# Sheet1_GMAX4651_MB.net
KiCad netlist of a schematic drawn in Altium Designer
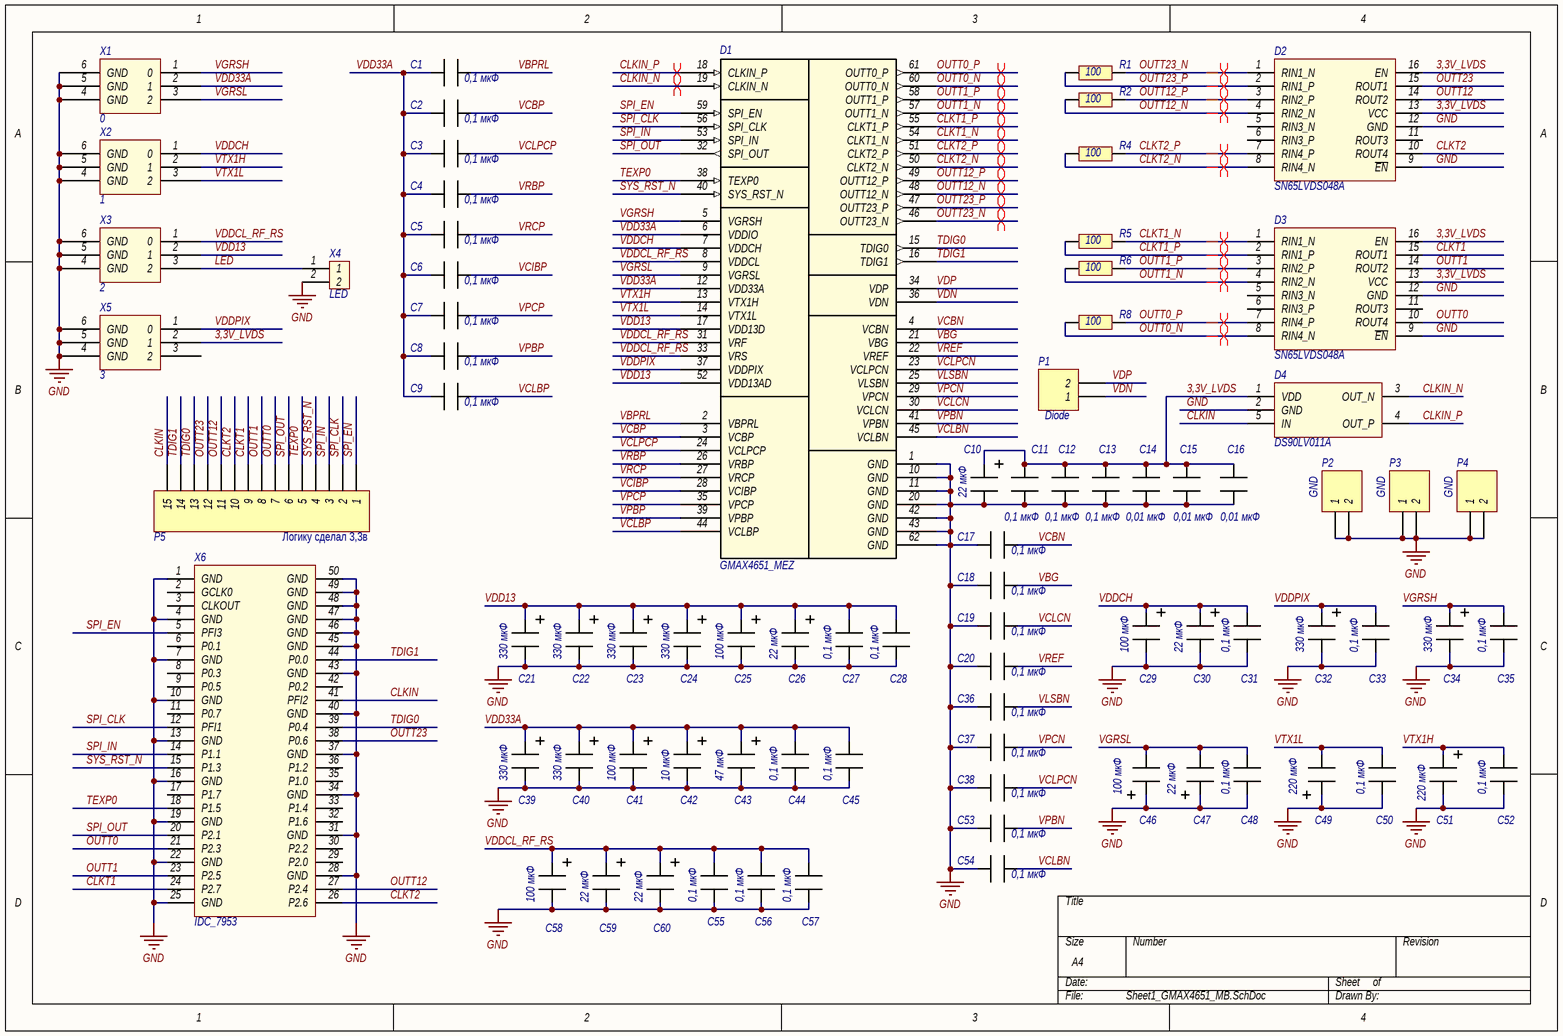
[diagram p0: Sheet1_GMAX4651_MB.SchDoc]

(export (version "E")
  (design (tool "Eeschema 10.0.6"))
  (components
    (comp (ref "C1") (value "0,1 мкФ") (footprint "CAP_SMALL") (libsource (lib "Schlib") (part "CAP_SMALL")))
    (comp (ref "C2") (value "0,1 мкФ") (footprint "CAP_SMALL") (libsource (lib "Schlib") (part "CAP_SMALL")))
    (comp (ref "C3") (value "0,1 мкФ") (footprint "CAP_SMALL") (libsource (lib "Schlib") (part "CAP_SMALL")))
    (comp (ref "C4") (value "0,1 мкФ") (footprint "CAP_SMALL") (libsource (lib "Schlib") (part "CAP_SMALL")))
    (comp (ref "C5") (value "0,1 мкФ") (footprint "CAP_SMALL") (libsource (lib "Schlib") (part "CAP_SMALL")))
    (comp (ref "C6") (value "0,1 мкФ") (footprint "CAP_SMALL") (libsource (lib "Schlib") (part "CAP_SMALL")))
    (comp (ref "C7") (value "0,1 мкФ") (footprint "CAP_SMALL") (libsource (lib "Schlib") (part "CAP_SMALL")))
    (comp (ref "C8") (value "0,1 мкФ") (footprint "CAP_SMALL") (libsource (lib "Schlib") (part "CAP_SMALL")))
    (comp (ref "C9") (value "0,1 мкФ") (footprint "CAP_SMALL") (libsource (lib "Schlib") (part "CAP_SMALL")))
    (comp (ref "C10")
      (value "22 мкФ")
      (footprint "Cap_0511_electrolitic")
      (libsource (lib "Schlib") (part "Cap_electrolotoc_0511"))
    )
    (comp (ref "C11") (value "0,1 мкФ") (footprint "CAP_SMALL") (libsource (lib "Schlib") (part "CAP_SMALL")))
    (comp (ref "C12") (value "0,1 мкФ") (footprint "CAP_SMALL") (libsource (lib "Schlib") (part "CAP_SMALL")))
    (comp (ref "C13") (value "0,1 мкФ") (footprint "CAP_SMALL") (libsource (lib "Schlib") (part "CAP_SMALL")))
    (comp (ref "C14")
      (value "0,01 мкФ")
      (footprint "CAP_SMALL")
      (libsource (lib "Schlib") (part "CAP_SMALL"))
    )
    (comp (ref "C15")
      (value "0,01 мкФ")
      (footprint "CAP_SMALL")
      (libsource (lib "Schlib") (part "CAP_SMALL"))
    )
    (comp (ref "C16")
      (value "0,01 мкФ")
      (footprint "CAP_SMALL")
      (libsource (lib "Schlib") (part "CAP_SMALL"))
    )
    (comp (ref "C17") (value "0,1 мкФ") (footprint "CAP_SMALL") (libsource (lib "Schlib") (part "CAP_SMALL")))
    (comp (ref "C18") (value "0,1 мкФ") (footprint "CAP_SMALL") (libsource (lib "Schlib") (part "CAP_SMALL")))
    (comp (ref "C19") (value "0,1 мкФ") (footprint "CAP_SMALL") (libsource (lib "Schlib") (part "CAP_SMALL")))
    (comp (ref "C20") (value "0,1 мкФ") (footprint "CAP_SMALL") (libsource (lib "Schlib") (part "CAP_SMALL")))
    (comp (ref "C21")
      (value "330 мкФ")
      (footprint "Cap_1013_electrolitic")
      (libsource (lib "Schlib") (part "Cap_electrolotoc_1013"))
    )
    (comp (ref "C22")
      (value "330 мкФ")
      (footprint "Cap_1013_electrolitic")
      (libsource (lib "Schlib") (part "Cap_electrolotoc_1013"))
    )
    (comp (ref "C23")
      (value "330 мкФ")
      (footprint "Cap_1013_electrolitic")
      (libsource (lib "Schlib") (part "Cap_electrolotoc_1013"))
    )
    (comp (ref "C24")
      (value "330 мкФ")
      (footprint "Cap_1013_electrolitic")
      (libsource (lib "Schlib") (part "Cap_electrolotoc_1013"))
    )
    (comp (ref "C25")
      (value "100 мкФ")
      (footprint "Cap_0612_electrolitic")
      (libsource (lib "Schlib") (part "Cap_electrolotoc_0612"))
    )
    (comp (ref "C26")
      (value "22 мкФ")
      (footprint "Cap_0511_electrolitic")
      (libsource (lib "Schlib") (part "Cap_electrolotoc_0511"))
    )
    (comp (ref "C27") (value "0,1 мкФ") (footprint "CAP_SMALL") (libsource (lib "Schlib") (part "CAP_SMALL")))
    (comp (ref "C28") (value "0,1 мкФ") (footprint "CAP_SMALL") (libsource (lib "Schlib") (part "CAP_SMALL")))
    (comp (ref "C29")
      (value "100 мкФ")
      (footprint "Cap_0612_electrolitic")
      (libsource (lib "Schlib") (part "Cap_electrolotoc_0612"))
    )
    (comp (ref "C30")
      (value "22 мкФ")
      (footprint "Cap_0511_electrolitic")
      (libsource (lib "Schlib") (part "Cap_electrolotoc_0511"))
    )
    (comp (ref "C31") (value "0,1 мкФ") (footprint "CAP_SMALL") (libsource (lib "Schlib") (part "CAP_SMALL")))
    (comp (ref "C32")
      (value "330 мкФ")
      (footprint "Cap_1013_electrolitic")
      (libsource (lib "Schlib") (part "Cap_electrolotoc_1013"))
    )
    (comp (ref "C33") (value "0,1 мкФ") (footprint "CAP_SMALL") (libsource (lib "Schlib") (part "CAP_SMALL")))
    (comp (ref "C34")
      (value "330 мкФ")
      (footprint "Cap_1013_electrolitic")
      (libsource (lib "Schlib") (part "Cap_electrolotoc_1013"))
    )
    (comp (ref "C35") (value "0,1 мкФ") (footprint "CAP_SMALL") (libsource (lib "Schlib") (part "CAP_SMALL")))
    (comp (ref "C36") (value "0,1 мкФ") (footprint "CAP_SMALL") (libsource (lib "Schlib") (part "CAP_SMALL")))
    (comp (ref "C37") (value "0,1 мкФ") (footprint "CAP_SMALL") (libsource (lib "Schlib") (part "CAP_SMALL")))
    (comp (ref "C38") (value "0,1 мкФ") (footprint "CAP_SMALL") (libsource (lib "Schlib") (part "CAP_SMALL")))
    (comp (ref "C39")
      (value "330 мкФ")
      (footprint "Cap_1013_electrolitic")
      (libsource (lib "Schlib") (part "Cap_electrolotoc_1013"))
    )
    (comp (ref "C40")
      (value "330 мкФ")
      (footprint "Cap_1013_electrolitic")
      (libsource (lib "Schlib") (part "Cap_electrolotoc_1013"))
    )
    (comp (ref "C41")
      (value "100 мкФ")
      (footprint "Cap_0612_electrolitic")
      (libsource (lib "Schlib") (part "Cap_electrolotoc_0612"))
    )
    (comp (ref "C42")
      (value "10 мкФ")
      (footprint "Cap_0511_electrolitic")
      (libsource (lib "Schlib") (part "Cap_electrolotoc_0511"))
    )
    (comp (ref "C43")
      (value "47 мкФ")
      (footprint "Cap_0612_electrolitic")
      (libsource (lib "Schlib") (part "Cap_electrolotoc_0612"))
    )
    (comp (ref "C44") (value "0,1 мкФ") (footprint "CAP_SMALL") (libsource (lib "Schlib") (part "CAP_SMALL")))
    (comp (ref "C45") (value "0,1 мкФ") (footprint "CAP_SMALL") (libsource (lib "Schlib") (part "CAP_SMALL")))
    (comp (ref "C46")
      (value "100 мкФ")
      (footprint "Cap_0612_electrolitic")
      (libsource (lib "Schlib") (part "Cap_electrolotoc_0612"))
    )
    (comp (ref "C47")
      (value "22 мкФ")
      (footprint "Cap_0511_electrolitic")
      (libsource (lib "Schlib") (part "Cap_electrolotoc_0511"))
    )
    (comp (ref "C48") (value "0,1 мкФ") (footprint "CAP_SMALL") (libsource (lib "Schlib") (part "CAP_SMALL")))
    (comp (ref "C49")
      (value "220 мкФ")
      (footprint "Cap_1013_electrolitic")
      (libsource (lib "Schlib") (part "Cap_electrolotoc_1013"))
    )
    (comp (ref "C50") (value "0,1 мкФ") (footprint "CAP_SMALL") (libsource (lib "Schlib") (part "CAP_SMALL")))
    (comp (ref "C51")
      (value "220 мкФ")
      (footprint "Cap_1013_electrolitic")
      (libsource (lib "Schlib") (part "Cap_electrolotoc_1013"))
    )
    (comp (ref "C52") (value "0,1 мкФ") (footprint "CAP_SMALL") (libsource (lib "Schlib") (part "CAP_SMALL")))
    (comp (ref "C53") (value "0,1 мкФ") (footprint "CAP_SMALL") (libsource (lib "Schlib") (part "CAP_SMALL")))
    (comp (ref "C54") (value "0,1 мкФ") (footprint "CAP_SMALL") (libsource (lib "Schlib") (part "CAP_SMALL")))
    (comp (ref "C55") (value "0,1 мкФ") (footprint "CAP_SMALL") (libsource (lib "Schlib") (part "CAP_SMALL")))
    (comp (ref "C56") (value "0,1 мкФ") (footprint "CAP_SMALL") (libsource (lib "Schlib") (part "CAP_SMALL")))
    (comp (ref "C57") (value "0,1 мкФ") (footprint "CAP_SMALL") (libsource (lib "Schlib") (part "CAP_SMALL")))
    (comp (ref "C58")
      (value "100 мкФ")
      (footprint "Cap_0612_electrolitic")
      (libsource (lib "Schlib") (part "Cap_electrolotoc_0612"))
    )
    (comp (ref "C59")
      (value "22 мкФ")
      (footprint "Cap_0511_electrolitic")
      (libsource (lib "Schlib") (part "Cap_electrolotoc_0511"))
    )
    (comp (ref "C60")
      (value "22 мкФ")
      (footprint "Cap_0511_electrolitic")
      (libsource (lib "Schlib") (part "Cap_electrolotoc_0511"))
    )
    (comp (ref "D1")
      (value "GMAX4651_MEZ")
      (footprint "GMAX4651_MEZ")
      (libsource (lib "Schlib") (part "GMAX4651_MEZ"))
    )
    (comp (ref "D2")
      (value "SN65LVDS048A")
      (footprint "SN65LVDS048A (4LVDS)")
      (libsource (lib "Schlib") (part "SN65LVDS048A (4LVDS)"))
    )
    (comp (ref "D3")
      (value "SN65LVDS048A")
      (footprint "SN65LVDS048A (4LVDS)")
      (libsource (lib "Schlib") (part "SN65LVDS048A (4LVDS)"))
    )
    (comp (ref "D4")
      (value "DS90LV011A")
      (footprint "DS90LV011A")
      (description "LVDS Driver 1 ch")
      (libsource (lib "Schlib") (part "DS90LV011A"))
    )
    (comp (ref "P1")
      (value "Diode")
      (footprint "HDR1X2")
      (description "Header, 2-Pin")
      (fields (field (name "PUBLISHER") "Altium Limited"))
      (libsource (lib "Miscellaneous Connectors") (part "Header 2"))
    )
    (comp (ref "P2")
      (value "GND")
      (footprint "HDR1X2")
      (description "Header, 2-Pin")
      (fields (field (name "PUBLISHER") "Altium Limited"))
      (libsource (lib "") (part "Header 2_1"))
    )
    (comp (ref "P3")
      (value "GND")
      (footprint "HDR1X2")
      (description "Header, 2-Pin")
      (fields (field (name "PUBLISHER") "Altium Limited"))
      (libsource (lib "") (part "Header 2_1"))
    )
    (comp (ref "P4")
      (value "GND")
      (footprint "HDR1X2")
      (description "Header, 2-Pin")
      (fields (field (name "PUBLISHER") "Altium Limited"))
      (libsource (lib "") (part "Header 2_1"))
    )
    (comp (ref "P5")
      (value "Header 15")
      (footprint "HDR1X15")
      (description "Header, 15-Pin")
      (fields (field (name "PUBLISHER") "Altium Limited"))
      (libsource (lib "Miscellaneous Connectors") (part "Header 15"))
    )
    (comp (ref "R1") (value "100") (footprint "RES") (libsource (lib "Schlib") (part "RES")))
    (comp (ref "R2") (value "100") (footprint "RES") (libsource (lib "Schlib") (part "RES")))
    (comp (ref "R4") (value "100") (footprint "RES") (libsource (lib "Schlib") (part "RES")))
    (comp (ref "R5") (value "100") (footprint "RES") (libsource (lib "Schlib") (part "RES")))
    (comp (ref "R6") (value "100") (footprint "RES") (libsource (lib "Schlib") (part "RES")))
    (comp (ref "R8") (value "100") (footprint "RES") (libsource (lib "Schlib") (part "RES")))
    (comp (ref "X1") (value "0") (footprint "POWER") (libsource (lib "Schlib") (part "POWER")))
    (comp (ref "X2") (value "1") (footprint "POWER") (libsource (lib "Schlib") (part "POWER")))
    (comp (ref "X3") (value "2") (footprint "POWER") (libsource (lib "Schlib") (part "POWER")))
    (comp (ref "X4") (value "LED") (footprint "KLEMMNIK_2") (libsource (lib "Schlib") (part "KLEMMNIK_2")))
    (comp (ref "X5") (value "3") (footprint "POWER") (libsource (lib "Schlib") (part "POWER")))
    (comp (ref "X6") (value "IDC_7953") (footprint "IDC_7953") (libsource (lib "VPL") (part "IDC_7953")))
  )
  (nets
    (net (code "1") (name "/3,3V_LVDS") (class "Default")
      (node (ref "C10") (pin "1") (pinfunction "1_1") (pintype "passive"))
      (node (ref "C11") (pin "2") (pinfunction "2_2") (pintype "passive"))
      (node (ref "C12") (pin "2") (pinfunction "2_2") (pintype "passive"))
      (node (ref "C13") (pin "2") (pinfunction "2_2") (pintype "passive"))
      (node (ref "C14") (pin "2") (pinfunction "2_2") (pintype "passive"))
      (node (ref "C15") (pin "2") (pinfunction "2_2") (pintype "passive"))
      (node (ref "C16") (pin "2") (pinfunction "2_2") (pintype "passive"))
      (node (ref "D2") (pin "13") (pinfunction "VCC_13") (pintype "passive"))
      (node (ref "D2") (pin "16") (pinfunction "EN_16") (pintype "passive"))
      (node (ref "D3") (pin "13") (pinfunction "VCC_13") (pintype "passive"))
      (node (ref "D3") (pin "16") (pinfunction "EN_16") (pintype "passive"))
      (node (ref "D4") (pin "1") (pinfunction "VDD_1") (pintype "passive"))
      (node (ref "X5") (pin "2") (pinfunction "1_2") (pintype "passive"))
    )
    (net (code "2") (name "/CLKIN") (class "Default")
      (node (ref "D4") (pin "5") (pinfunction "IN_5") (pintype "passive"))
      (node (ref "P5") (pin "15") (pinfunction "15_15") (pintype "passive"))
      (node (ref "X6") (pin "41") (pinfunction "PFI2_41") (pintype "passive"))
    )
    (net (code "3") (name "/CLKIN_N") (class "Default")
      (node (ref "D1") (pin "19") (pinfunction "CLKIN_N_19") (pintype "input"))
      (node (ref "D4") (pin "3") (pinfunction "OUT_N_3") (pintype "passive"))
    )
    (net (code "4") (name "/CLKIN_P") (class "Default")
      (node (ref "D1") (pin "18") (pinfunction "CLKIN_P_18") (pintype "input"))
      (node (ref "D4") (pin "4") (pinfunction "OUT_P_4") (pintype "passive"))
    )
    (net (code "5") (name "/CLKT1") (class "Default")
      (node (ref "D3") (pin "15") (pinfunction "ROUT1_15") (pintype "passive"))
      (node (ref "P5") (pin "9") (pinfunction "9_9") (pintype "passive"))
      (node (ref "X6") (pin "24") (pinfunction "P2.7_24") (pintype "passive"))
    )
    (net (code "6") (name "/CLKT1_N") (class "Default")
      (node (ref "D1") (pin "54") (pinfunction "CLKT1_N_54") (pintype "output"))
      (node (ref "D3") (pin "1") (pinfunction "RIN1_N_1") (pintype "passive"))
      (node (ref "R5") (pin "1") (pinfunction "1_1") (pintype "passive"))
    )
    (net (code "7") (name "/CLKT1_P") (class "Default")
      (node (ref "D1") (pin "55") (pinfunction "CLKT1_P_55") (pintype "output"))
      (node (ref "D3") (pin "2") (pinfunction "RIN1_P_2") (pintype "passive"))
      (node (ref "R5") (pin "2") (pinfunction "2_2") (pintype "passive"))
    )
    (net (code "8") (name "/CLKT2") (class "Default")
      (node (ref "D2") (pin "10") (pinfunction "ROUT4_10") (pintype "passive"))
      (node (ref "P5") (pin "10") (pinfunction "10_10") (pintype "passive"))
      (node (ref "X6") (pin "26") (pinfunction "P2.6_26") (pintype "passive"))
    )
    (net (code "9") (name "/CLKT2_N") (class "Default")
      (node (ref "D1") (pin "50") (pinfunction "CLKT2_N_50") (pintype "output"))
      (node (ref "D2") (pin "8") (pinfunction "RIN4_N_8") (pintype "passive"))
      (node (ref "R4") (pin "2") (pinfunction "2_2") (pintype "passive"))
    )
    (net (code "10") (name "/CLKT2_P") (class "Default")
      (node (ref "D1") (pin "51") (pinfunction "CLKT2_P_51") (pintype "output"))
      (node (ref "D2") (pin "7") (pinfunction "RIN4_P_7") (pintype "passive"))
      (node (ref "R4") (pin "1") (pinfunction "1_1") (pintype "passive"))
    )
    (net (code "11") (name "/LED") (class "Default")
      (node (ref "X3") (pin "3") (pinfunction "2_3") (pintype "passive"))
      (node (ref "X4") (pin "1") (pinfunction "1_1") (pintype "passive"))
    )
    (net (code "12") (name "/OUTT0") (class "Default")
      (node (ref "D3") (pin "10") (pinfunction "ROUT4_10") (pintype "passive"))
      (node (ref "P5") (pin "7") (pinfunction "7_7") (pintype "passive"))
      (node (ref "X6") (pin "21") (pinfunction "P2.3_21") (pintype "passive"))
    )
    (net (code "13") (name "/OUTT0_N") (class "Default")
      (node (ref "D1") (pin "60") (pinfunction "OUTT0_N_60") (pintype "output"))
      (node (ref "D3") (pin "8") (pinfunction "RIN4_N_8") (pintype "passive"))
      (node (ref "R8") (pin "2") (pinfunction "2_2") (pintype "passive"))
    )
    (net (code "14") (name "/OUTT0_P") (class "Default")
      (node (ref "D1") (pin "61") (pinfunction "OUTT0_P_61") (pintype "output"))
      (node (ref "D3") (pin "7") (pinfunction "RIN4_P_7") (pintype "passive"))
      (node (ref "R8") (pin "1") (pinfunction "1_1") (pintype "passive"))
    )
    (net (code "15") (name "/OUTT1") (class "Default")
      (node (ref "D3") (pin "14") (pinfunction "ROUT2_14") (pintype "passive"))
      (node (ref "P5") (pin "8") (pinfunction "8_8") (pintype "passive"))
      (node (ref "X6") (pin "23") (pinfunction "P2.5_23") (pintype "passive"))
    )
    (net (code "16") (name "/OUTT1_N") (class "Default")
      (node (ref "D1") (pin "57") (pinfunction "OUTT1_N_57") (pintype "output"))
      (node (ref "D3") (pin "4") (pinfunction "RIN2_N_4") (pintype "passive"))
      (node (ref "R6") (pin "2") (pinfunction "2_2") (pintype "passive"))
    )
    (net (code "17") (name "/OUTT1_P") (class "Default")
      (node (ref "D1") (pin "58") (pinfunction "OUTT1_P_58") (pintype "output"))
      (node (ref "D3") (pin "3") (pinfunction "RIN2_P_3") (pintype "passive"))
      (node (ref "R6") (pin "1") (pinfunction "1_1") (pintype "passive"))
    )
    (net (code "18") (name "/OUTT12") (class "Default")
      (node (ref "D2") (pin "14") (pinfunction "ROUT2_14") (pintype "passive"))
      (node (ref "P5") (pin "11") (pinfunction "11_11") (pintype "passive"))
      (node (ref "X6") (pin "27") (pinfunction "P2.4_27") (pintype "passive"))
    )
    (net (code "19") (name "/OUTT12_N") (class "Default")
      (node (ref "D1") (pin "48") (pinfunction "OUTT12_N_48") (pintype "output"))
      (node (ref "D2") (pin "4") (pinfunction "RIN2_N_4") (pintype "passive"))
      (node (ref "R2") (pin "2") (pinfunction "2_2") (pintype "passive"))
    )
    (net (code "20") (name "/OUTT12_P") (class "Default")
      (node (ref "D1") (pin "49") (pinfunction "OUTT12_P_49") (pintype "output"))
      (node (ref "D2") (pin "3") (pinfunction "RIN2_P_3") (pintype "passive"))
      (node (ref "R2") (pin "1") (pinfunction "1_1") (pintype "passive"))
    )
    (net (code "21") (name "/OUTT23") (class "Default")
      (node (ref "D2") (pin "15") (pinfunction "ROUT1_15") (pintype "passive"))
      (node (ref "P5") (pin "12") (pinfunction "12_12") (pintype "passive"))
      (node (ref "X6") (pin "38") (pinfunction "P0.6_38") (pintype "passive"))
    )
    (net (code "22") (name "/OUTT23_N") (class "Default")
      (node (ref "D1") (pin "46") (pinfunction "OUTT23_N_46") (pintype "output"))
      (node (ref "D2") (pin "1") (pinfunction "RIN1_N_1") (pintype "passive"))
      (node (ref "R1") (pin "1") (pinfunction "1_1") (pintype "passive"))
    )
    (net (code "23") (name "/OUTT23_P") (class "Default")
      (node (ref "D1") (pin "47") (pinfunction "OUTT23_P_47") (pintype "output"))
      (node (ref "D2") (pin "2") (pinfunction "RIN1_P_2") (pintype "passive"))
      (node (ref "R1") (pin "2") (pinfunction "2_2") (pintype "passive"))
    )
    (net (code "24") (name "/SPI_CLK") (class "Default")
      (node (ref "D1") (pin "56") (pinfunction "SPI_CLK_56") (pintype "input"))
      (node (ref "P5") (pin "2") (pinfunction "2_2") (pintype "passive"))
      (node (ref "X6") (pin "12") (pinfunction "PFI1_12") (pintype "passive"))
    )
    (net (code "25") (name "/SPI_EN") (class "Default")
      (node (ref "D1") (pin "59") (pinfunction "SPI_EN_59") (pintype "input"))
      (node (ref "P5") (pin "1") (pinfunction "1_1") (pintype "passive"))
      (node (ref "X6") (pin "5") (pinfunction "PFI3_5") (pintype "passive"))
    )
    (net (code "26") (name "/SPI_IN") (class "Default")
      (node (ref "D1") (pin "53") (pinfunction "SPI_IN_53") (pintype "input"))
      (node (ref "P5") (pin "3") (pinfunction "3_3") (pintype "passive"))
      (node (ref "X6") (pin "14") (pinfunction "P1.1_14") (pintype "passive"))
    )
    (net (code "27") (name "/SPI_OUT") (class "Default")
      (node (ref "D1") (pin "32") (pinfunction "SPI_OUT_32") (pintype "output"))
      (node (ref "P5") (pin "6") (pinfunction "6_6") (pintype "passive"))
      (node (ref "X6") (pin "20") (pinfunction "P2.1_20") (pintype "passive"))
    )
    (net (code "28") (name "/SYS_RST_N") (class "Default")
      (node (ref "D1") (pin "40") (pinfunction "SYS_RST_N_40") (pintype "input"))
      (node (ref "P5") (pin "4") (pinfunction "4_4") (pintype "passive"))
      (node (ref "X6") (pin "15") (pinfunction "P1.3_15") (pintype "passive"))
    )
    (net (code "29") (name "/TDIG0") (class "Default")
      (node (ref "D1") (pin "15") (pinfunction "TDIG0_15") (pintype "output"))
      (node (ref "P5") (pin "13") (pinfunction "13_13") (pintype "passive"))
      (node (ref "X6") (pin "39") (pinfunction "P0.4_39") (pintype "passive"))
    )
    (net (code "30") (name "/TDIG1") (class "Default")
      (node (ref "D1") (pin "16") (pinfunction "TDIG1_16") (pintype "output"))
      (node (ref "P5") (pin "14") (pinfunction "14_14") (pintype "passive"))
      (node (ref "X6") (pin "44") (pinfunction "P0.0_44") (pintype "passive"))
    )
    (net (code "31") (name "/TEXP0") (class "Default")
      (node (ref "D1") (pin "38") (pinfunction "TEXP0_38") (pintype "input"))
      (node (ref "P5") (pin "5") (pinfunction "5_5") (pintype "passive"))
      (node (ref "X6") (pin "18") (pinfunction "P1.5_18") (pintype "passive"))
    )
    (net (code "32") (name "/VBG") (class "Default")
      (node (ref "C18") (pin "1") (pinfunction "1_1") (pintype "passive"))
      (node (ref "D1") (pin "21") (pinfunction "VBG_21") (pintype "passive"))
    )
    (net (code "33") (name "/VBPRL") (class "Default")
      (node (ref "C1") (pin "1") (pinfunction "1_1") (pintype "passive"))
      (node (ref "D1") (pin "2") (pinfunction "VBPRL_2") (pintype "passive"))
    )
    (net (code "34") (name "/VCBN") (class "Default")
      (node (ref "C17") (pin "1") (pinfunction "1_1") (pintype "passive"))
      (node (ref "D1") (pin "4") (pinfunction "VCBN_4") (pintype "passive"))
    )
    (net (code "35") (name "/VCBP") (class "Default")
      (node (ref "C2") (pin "1") (pinfunction "1_1") (pintype "passive"))
      (node (ref "D1") (pin "3") (pinfunction "VCBP_3") (pintype "passive"))
    )
    (net (code "36") (name "/VCIBP") (class "Default")
      (node (ref "C6") (pin "1") (pinfunction "1_1") (pintype "passive"))
      (node (ref "D1") (pin "28") (pinfunction "VCIBP_28") (pintype "passive"))
    )
    (net (code "37") (name "/VCLBN") (class "Default")
      (node (ref "C54") (pin "1") (pinfunction "1_1") (pintype "passive"))
      (node (ref "D1") (pin "45") (pinfunction "VCLBN_45") (pintype "passive"))
    )
    (net (code "38") (name "/VCLBP") (class "Default")
      (node (ref "C9") (pin "1") (pinfunction "1_1") (pintype "passive"))
      (node (ref "D1") (pin "44") (pinfunction "VCLBP_44") (pintype "passive"))
    )
    (net (code "39") (name "/VCLCN") (class "Default")
      (node (ref "C19") (pin "1") (pinfunction "1_1") (pintype "passive"))
      (node (ref "D1") (pin "30") (pinfunction "VCLCN_30") (pintype "passive"))
    )
    (net (code "40") (name "/VCLPCN") (class "Default")
      (node (ref "C38") (pin "1") (pinfunction "1_1") (pintype "passive"))
      (node (ref "D1") (pin "23") (pinfunction "VCLPCN_23") (pintype "passive"))
    )
    (net (code "41") (name "/VCLPCP") (class "Default")
      (node (ref "C3") (pin "1") (pinfunction "1_1") (pintype "passive"))
      (node (ref "D1") (pin "24") (pinfunction "VCLPCP_24") (pintype "passive"))
    )
    (net (code "42") (name "/VDD13") (class "Default")
      (node (ref "C21") (pin "1") (pinfunction "1_1") (pintype "passive"))
      (node (ref "C22") (pin "1") (pinfunction "1_1") (pintype "passive"))
      (node (ref "C23") (pin "1") (pinfunction "1_1") (pintype "passive"))
      (node (ref "C24") (pin "1") (pinfunction "1_1") (pintype "passive"))
      (node (ref "C25") (pin "1") (pinfunction "1_1") (pintype "passive"))
      (node (ref "C26") (pin "1") (pinfunction "1_1") (pintype "passive"))
      (node (ref "C27") (pin "1") (pinfunction "1_1") (pintype "passive"))
      (node (ref "C28") (pin "1") (pinfunction "1_1") (pintype "passive"))
      (node (ref "D1") (pin "17") (pinfunction "VDD13D_17") (pintype "passive"))
      (node (ref "D1") (pin "52") (pinfunction "VDD13AD_52") (pintype "passive"))
      (node (ref "X3") (pin "2") (pinfunction "1_2") (pintype "passive"))
    )
    (net (code "43") (name "/VDD33A") (class "Default")
      (node (ref "C1") (pin "2") (pinfunction "2_2") (pintype "passive"))
      (node (ref "C2") (pin "2") (pinfunction "2_2") (pintype "passive"))
      (node (ref "C3") (pin "2") (pinfunction "2_2") (pintype "passive"))
      (node (ref "C39") (pin "1") (pinfunction "1_1") (pintype "passive"))
      (node (ref "C4") (pin "2") (pinfunction "2_2") (pintype "passive"))
      (node (ref "C40") (pin "1") (pinfunction "1_1") (pintype "passive"))
      (node (ref "C41") (pin "1") (pinfunction "1_1") (pintype "passive"))
      (node (ref "C42") (pin "1") (pinfunction "1_1") (pintype "passive"))
      (node (ref "C43") (pin "1") (pinfunction "1_1") (pintype "passive"))
      (node (ref "C44") (pin "1") (pinfunction "1_1") (pintype "passive"))
      (node (ref "C45") (pin "1") (pinfunction "1_1") (pintype "passive"))
      (node (ref "C5") (pin "2") (pinfunction "2_2") (pintype "passive"))
      (node (ref "C6") (pin "2") (pinfunction "2_2") (pintype "passive"))
      (node (ref "C7") (pin "2") (pinfunction "2_2") (pintype "passive"))
      (node (ref "C8") (pin "2") (pinfunction "2_2") (pintype "passive"))
      (node (ref "C9") (pin "2") (pinfunction "2_2") (pintype "passive"))
      (node (ref "D1") (pin "12") (pinfunction "VDD33A_12") (pintype "passive"))
      (node (ref "D1") (pin "6") (pinfunction "VDDIO_6") (pintype "passive"))
      (node (ref "X1") (pin "2") (pinfunction "1_2") (pintype "passive"))
    )
    (net (code "44") (name "/VDDCH") (class "Default")
      (node (ref "C29") (pin "1") (pinfunction "1_1") (pintype "passive"))
      (node (ref "C30") (pin "1") (pinfunction "1_1") (pintype "passive"))
      (node (ref "C31") (pin "1") (pinfunction "1_1") (pintype "passive"))
      (node (ref "D1") (pin "7") (pinfunction "VDDCH_7") (pintype "passive"))
      (node (ref "X2") (pin "1") (pinfunction "0_1") (pintype "passive"))
    )
    (net (code "45") (name "/VDDCL_RF_RS") (class "Default")
      (node (ref "C55") (pin "1") (pinfunction "1_1") (pintype "passive"))
      (node (ref "C56") (pin "1") (pinfunction "1_1") (pintype "passive"))
      (node (ref "C57") (pin "1") (pinfunction "1_1") (pintype "passive"))
      (node (ref "C58") (pin "1") (pinfunction "1_1") (pintype "passive"))
      (node (ref "C59") (pin "1") (pinfunction "1_1") (pintype "passive"))
      (node (ref "C60") (pin "1") (pinfunction "1_1") (pintype "passive"))
      (node (ref "D1") (pin "31") (pinfunction "VRF_31") (pintype "passive"))
      (node (ref "D1") (pin "33") (pinfunction "VRS_33") (pintype "passive"))
      (node (ref "D1") (pin "8") (pinfunction "VDDCL_8") (pintype "passive"))
      (node (ref "X3") (pin "1") (pinfunction "0_1") (pintype "passive"))
    )
    (net (code "46") (name "/VDDPIX") (class "Default")
      (node (ref "C32") (pin "1") (pinfunction "1_1") (pintype "passive"))
      (node (ref "C33") (pin "1") (pinfunction "1_1") (pintype "passive"))
      (node (ref "D1") (pin "37") (pinfunction "VDDPIX_37") (pintype "passive"))
      (node (ref "X5") (pin "1") (pinfunction "0_1") (pintype "passive"))
    )
    (net (code "47") (name "/VDN") (class "Default")
      (node (ref "D1") (pin "36") (pinfunction "VDN_36") (pintype "passive"))
      (node (ref "P1") (pin "1") (pinfunction "1_1") (pintype "passive"))
    )
    (net (code "48") (name "/VDP") (class "Default")
      (node (ref "D1") (pin "34") (pinfunction "VDP_34") (pintype "passive"))
      (node (ref "P1") (pin "2") (pinfunction "2_2") (pintype "passive"))
    )
    (net (code "49") (name "/VGRSH") (class "Default")
      (node (ref "C34") (pin "1") (pinfunction "1_1") (pintype "passive"))
      (node (ref "C35") (pin "1") (pinfunction "1_1") (pintype "passive"))
      (node (ref "D1") (pin "5") (pinfunction "VGRSH_5") (pintype "passive"))
      (node (ref "X1") (pin "1") (pinfunction "0_1") (pintype "passive"))
    )
    (net (code "50") (name "/VGRSL") (class "Default")
      (node (ref "C46") (pin "2") (pinfunction "2_2") (pintype "passive"))
      (node (ref "C47") (pin "2") (pinfunction "2_2") (pintype "passive"))
      (node (ref "C48") (pin "1") (pinfunction "1_1") (pintype "passive"))
      (node (ref "D1") (pin "9") (pinfunction "VGRSL_9") (pintype "passive"))
      (node (ref "X1") (pin "3") (pinfunction "2_3") (pintype "passive"))
    )
    (net (code "51") (name "/VLSBN") (class "Default")
      (node (ref "C36") (pin "1") (pinfunction "1_1") (pintype "passive"))
      (node (ref "D1") (pin "25") (pinfunction "VLSBN_25") (pintype "passive"))
    )
    (net (code "52") (name "/VPBN") (class "Default")
      (node (ref "C53") (pin "1") (pinfunction "1_1") (pintype "passive"))
      (node (ref "D1") (pin "41") (pinfunction "VPBN_41") (pintype "passive"))
    )
    (net (code "53") (name "/VPBP") (class "Default")
      (node (ref "C8") (pin "1") (pinfunction "1_1") (pintype "passive"))
      (node (ref "D1") (pin "39") (pinfunction "VPBP_39") (pintype "passive"))
    )
    (net (code "54") (name "/VPCN") (class "Default")
      (node (ref "C37") (pin "1") (pinfunction "1_1") (pintype "passive"))
      (node (ref "D1") (pin "29") (pinfunction "VPCN_29") (pintype "passive"))
    )
    (net (code "55") (name "/VPCP") (class "Default")
      (node (ref "C7") (pin "1") (pinfunction "1_1") (pintype "passive"))
      (node (ref "D1") (pin "35") (pinfunction "VPCP_35") (pintype "passive"))
    )
    (net (code "56") (name "/VRBP") (class "Default")
      (node (ref "C4") (pin "1") (pinfunction "1_1") (pintype "passive"))
      (node (ref "D1") (pin "26") (pinfunction "VRBP_26") (pintype "passive"))
    )
    (net (code "57") (name "/VRCP") (class "Default")
      (node (ref "C5") (pin "1") (pinfunction "1_1") (pintype "passive"))
      (node (ref "D1") (pin "27") (pinfunction "VRCP_27") (pintype "passive"))
    )
    (net (code "58") (name "/VREF") (class "Default")
      (node (ref "C20") (pin "1") (pinfunction "1_1") (pintype "passive"))
      (node (ref "D1") (pin "22") (pinfunction "VREF_22") (pintype "passive"))
    )
    (net (code "59") (name "/VTX1H") (class "Default")
      (node (ref "C51") (pin "1") (pinfunction "1_1") (pintype "passive"))
      (node (ref "C52") (pin "1") (pinfunction "1_1") (pintype "passive"))
      (node (ref "D1") (pin "13") (pinfunction "VTX1H_13") (pintype "passive"))
      (node (ref "X2") (pin "2") (pinfunction "1_2") (pintype "passive"))
    )
    (net (code "60") (name "/VTX1L") (class "Default")
      (node (ref "C49") (pin "2") (pinfunction "2_2") (pintype "passive"))
      (node (ref "C50") (pin "1") (pinfunction "1_1") (pintype "passive"))
      (node (ref "D1") (pin "14") (pinfunction "VTX1L_14") (pintype "passive"))
      (node (ref "X2") (pin "3") (pinfunction "2_3") (pintype "passive"))
    )
    (net (code "61") (name "GND") (class "Default")
      (node (ref "C10") (pin "2") (pinfunction "2_2") (pintype "passive"))
      (node (ref "C11") (pin "1") (pinfunction "1_1") (pintype "passive"))
      (node (ref "C12") (pin "1") (pinfunction "1_1") (pintype "passive"))
      (node (ref "C13") (pin "1") (pinfunction "1_1") (pintype "passive"))
      (node (ref "C14") (pin "1") (pinfunction "1_1") (pintype "passive"))
      (node (ref "C15") (pin "1") (pinfunction "1_1") (pintype "passive"))
      (node (ref "C16") (pin "1") (pinfunction "1_1") (pintype "passive"))
      (node (ref "C17") (pin "2") (pinfunction "2_2") (pintype "passive"))
      (node (ref "C18") (pin "2") (pinfunction "2_2") (pintype "passive"))
      (node (ref "C19") (pin "2") (pinfunction "2_2") (pintype "passive"))
      (node (ref "C20") (pin "2") (pinfunction "2_2") (pintype "passive"))
      (node (ref "C21") (pin "2") (pinfunction "2_2") (pintype "passive"))
      (node (ref "C22") (pin "2") (pinfunction "2_2") (pintype "passive"))
      (node (ref "C23") (pin "2") (pinfunction "2_2") (pintype "passive"))
      (node (ref "C24") (pin "2") (pinfunction "2_2") (pintype "passive"))
      (node (ref "C25") (pin "2") (pinfunction "2_2") (pintype "passive"))
      (node (ref "C26") (pin "2") (pinfunction "2_2") (pintype "passive"))
      (node (ref "C27") (pin "2") (pinfunction "2_2") (pintype "passive"))
      (node (ref "C28") (pin "2") (pinfunction "2_2") (pintype "passive"))
      (node (ref "C29") (pin "2") (pinfunction "2_2") (pintype "passive"))
      (node (ref "C30") (pin "2") (pinfunction "2_2") (pintype "passive"))
      (node (ref "C31") (pin "2") (pinfunction "2_2") (pintype "passive"))
      (node (ref "C32") (pin "2") (pinfunction "2_2") (pintype "passive"))
      (node (ref "C33") (pin "2") (pinfunction "2_2") (pintype "passive"))
      (node (ref "C34") (pin "2") (pinfunction "2_2") (pintype "passive"))
      (node (ref "C35") (pin "2") (pinfunction "2_2") (pintype "passive"))
      (node (ref "C36") (pin "2") (pinfunction "2_2") (pintype "passive"))
      (node (ref "C37") (pin "2") (pinfunction "2_2") (pintype "passive"))
      (node (ref "C38") (pin "2") (pinfunction "2_2") (pintype "passive"))
      (node (ref "C39") (pin "2") (pinfunction "2_2") (pintype "passive"))
      (node (ref "C40") (pin "2") (pinfunction "2_2") (pintype "passive"))
      (node (ref "C41") (pin "2") (pinfunction "2_2") (pintype "passive"))
      (node (ref "C42") (pin "2") (pinfunction "2_2") (pintype "passive"))
      (node (ref "C43") (pin "2") (pinfunction "2_2") (pintype "passive"))
      (node (ref "C44") (pin "2") (pinfunction "2_2") (pintype "passive"))
      (node (ref "C45") (pin "2") (pinfunction "2_2") (pintype "passive"))
      (node (ref "C46") (pin "1") (pinfunction "1_1") (pintype "passive"))
      (node (ref "C47") (pin "1") (pinfunction "1_1") (pintype "passive"))
      (node (ref "C48") (pin "2") (pinfunction "2_2") (pintype "passive"))
      (node (ref "C49") (pin "1") (pinfunction "1_1") (pintype "passive"))
      (node (ref "C50") (pin "2") (pinfunction "2_2") (pintype "passive"))
      (node (ref "C51") (pin "2") (pinfunction "2_2") (pintype "passive"))
      (node (ref "C52") (pin "2") (pinfunction "2_2") (pintype "passive"))
      (node (ref "C53") (pin "2") (pinfunction "2_2") (pintype "passive"))
      (node (ref "C54") (pin "2") (pinfunction "2_2") (pintype "passive"))
      (node (ref "C55") (pin "2") (pinfunction "2_2") (pintype "passive"))
      (node (ref "C56") (pin "2") (pinfunction "2_2") (pintype "passive"))
      (node (ref "C57") (pin "2") (pinfunction "2_2") (pintype "passive"))
      (node (ref "C58") (pin "2") (pinfunction "2_2") (pintype "passive"))
      (node (ref "C59") (pin "2") (pinfunction "2_2") (pintype "passive"))
      (node (ref "C60") (pin "2") (pinfunction "2_2") (pintype "passive"))
      (node (ref "D1") (pin "1") (pinfunction "GND_1") (pintype "passive"))
      (node (ref "D1") (pin "10") (pinfunction "GND_10") (pintype "passive"))
      (node (ref "D1") (pin "11") (pinfunction "GND_11") (pintype "passive"))
      (node (ref "D1") (pin "20") (pinfunction "GND_20") (pintype "passive"))
      (node (ref "D1") (pin "42") (pinfunction "GND_42") (pintype "passive"))
      (node (ref "D1") (pin "43") (pinfunction "GND_43") (pintype "passive"))
      (node (ref "D1") (pin "62") (pinfunction "GND_62") (pintype "passive"))
      (node (ref "D2") (pin "12") (pinfunction "GND_12") (pintype "passive"))
      (node (ref "D2") (pin "9") (pinfunction "~{EN}_9") (pintype "passive"))
      (node (ref "D3") (pin "12") (pinfunction "GND_12") (pintype "passive"))
      (node (ref "D3") (pin "9") (pinfunction "~{EN}_9") (pintype "passive"))
      (node (ref "D4") (pin "2") (pinfunction "GND_2") (pintype "passive"))
      (node (ref "P2") (pin "1") (pinfunction "1_1") (pintype "passive"))
      (node (ref "P2") (pin "2") (pinfunction "2_2") (pintype "passive"))
      (node (ref "P3") (pin "1") (pinfunction "1_1") (pintype "passive"))
      (node (ref "P3") (pin "2") (pinfunction "2_2") (pintype "passive"))
      (node (ref "P4") (pin "1") (pinfunction "1_1") (pintype "passive"))
      (node (ref "P4") (pin "2") (pinfunction "2_2") (pintype "passive"))
      (node (ref "X1") (pin "4") (pinfunction "GND_4") (pintype "passive"))
      (node (ref "X1") (pin "5") (pinfunction "GND_5") (pintype "passive"))
      (node (ref "X1") (pin "6") (pinfunction "GND_6") (pintype "passive"))
      (node (ref "X2") (pin "4") (pinfunction "GND_4") (pintype "passive"))
      (node (ref "X2") (pin "5") (pinfunction "GND_5") (pintype "passive"))
      (node (ref "X2") (pin "6") (pinfunction "GND_6") (pintype "passive"))
      (node (ref "X3") (pin "4") (pinfunction "GND_4") (pintype "passive"))
      (node (ref "X3") (pin "5") (pinfunction "GND_5") (pintype "passive"))
      (node (ref "X3") (pin "6") (pinfunction "GND_6") (pintype "passive"))
      (node (ref "X4") (pin "2") (pinfunction "2_2") (pintype "passive"))
      (node (ref "X5") (pin "4") (pinfunction "GND_4") (pintype "passive"))
      (node (ref "X5") (pin "5") (pinfunction "GND_5") (pintype "passive"))
      (node (ref "X5") (pin "6") (pinfunction "GND_6") (pintype "passive"))
      (node (ref "X6") (pin "1") (pinfunction "GND_1") (pintype "passive"))
      (node (ref "X6") (pin "10") (pinfunction "GND_10") (pintype "passive"))
      (node (ref "X6") (pin "13") (pinfunction "GND_13") (pintype "passive"))
      (node (ref "X6") (pin "16") (pinfunction "GND_16") (pintype "passive"))
      (node (ref "X6") (pin "19") (pinfunction "GND_19") (pintype "passive"))
      (node (ref "X6") (pin "22") (pinfunction "GND_22") (pintype "passive"))
      (node (ref "X6") (pin "25") (pinfunction "GND_25") (pintype "passive"))
      (node (ref "X6") (pin "28") (pinfunction "GND_28") (pintype "passive"))
      (node (ref "X6") (pin "31") (pinfunction "GND_31") (pintype "passive"))
      (node (ref "X6") (pin "34") (pinfunction "GND_34") (pintype "passive"))
      (node (ref "X6") (pin "37") (pinfunction "GND_37") (pintype "passive"))
      (node (ref "X6") (pin "4") (pinfunction "GND_4") (pintype "passive"))
      (node (ref "X6") (pin "40") (pinfunction "GND_40") (pintype "passive"))
      (node (ref "X6") (pin "43") (pinfunction "GND_43") (pintype "passive"))
      (node (ref "X6") (pin "45") (pinfunction "GND_45") (pintype "passive"))
      (node (ref "X6") (pin "46") (pinfunction "GND_46") (pintype "passive"))
      (node (ref "X6") (pin "47") (pinfunction "GND_47") (pintype "passive"))
      (node (ref "X6") (pin "48") (pinfunction "GND_48") (pintype "passive"))
      (node (ref "X6") (pin "49") (pinfunction "GND_49") (pintype "passive"))
      (node (ref "X6") (pin "50") (pinfunction "GND_50") (pintype "passive"))
      (node (ref "X6") (pin "7") (pinfunction "GND_7") (pintype "passive"))
    )
    (net (code "62") (name "unconnected-(D2-RIN3_N-Pad5)") (class "Default")
      (node (ref "D2") (pin "5") (pinfunction "RIN3_N_5") (pintype "passive"))
    )
    (net (code "63") (name "unconnected-(D2-RIN3_P-Pad6)") (class "Default")
      (node (ref "D2") (pin "6") (pinfunction "RIN3_P_6") (pintype "passive"))
    )
    (net (code "64") (name "unconnected-(D2-ROUT3-Pad11)") (class "Default")
      (node (ref "D2") (pin "11") (pinfunction "ROUT3_11") (pintype "passive"))
    )
    (net (code "65") (name "unconnected-(D3-RIN3_N-Pad5)") (class "Default")
      (node (ref "D3") (pin "5") (pinfunction "RIN3_N_5") (pintype "passive"))
    )
    (net (code "66") (name "unconnected-(D3-RIN3_P-Pad6)") (class "Default")
      (node (ref "D3") (pin "6") (pinfunction "RIN3_P_6") (pintype "passive"))
    )
    (net (code "67") (name "unconnected-(D3-ROUT3-Pad11)") (class "Default")
      (node (ref "D3") (pin "11") (pinfunction "ROUT3_11") (pintype "passive"))
    )
    (net (code "68") (name "unconnected-(X5-2-Pad3)") (class "Default")
      (node (ref "X5") (pin "3") (pinfunction "2_3") (pintype "passive"))
    )
    (net (code "69") (name "unconnected-(X6-CLKOUT-Pad3)") (class "Default")
      (node (ref "X6") (pin "3") (pinfunction "CLKOUT_3") (pintype "passive"))
    )
    (net (code "70") (name "unconnected-(X6-GCLK0-Pad2)") (class "Default")
      (node (ref "X6") (pin "2") (pinfunction "GCLK0_2") (pintype "passive"))
    )
    (net (code "71") (name "unconnected-(X6-P0.1-Pad6)") (class "Default")
      (node (ref "X6") (pin "6") (pinfunction "P0.1_6") (pintype "passive"))
    )
    (net (code "72") (name "unconnected-(X6-P0.2-Pad42)") (class "Default")
      (node (ref "X6") (pin "42") (pinfunction "P0.2_42") (pintype "passive"))
    )
    (net (code "73") (name "unconnected-(X6-P0.3-Pad8)") (class "Default")
      (node (ref "X6") (pin "8") (pinfunction "P0.3_8") (pintype "passive"))
    )
    (net (code "74") (name "unconnected-(X6-P0.5-Pad9)") (class "Default")
      (node (ref "X6") (pin "9") (pinfunction "P0.5_9") (pintype "passive"))
    )
    (net (code "75") (name "unconnected-(X6-P0.7-Pad11)") (class "Default")
      (node (ref "X6") (pin "11") (pinfunction "P0.7_11") (pintype "passive"))
    )
    (net (code "76") (name "unconnected-(X6-P1.0-Pad35)") (class "Default")
      (node (ref "X6") (pin "35") (pinfunction "P1.0_35") (pintype "passive"))
    )
    (net (code "77") (name "unconnected-(X6-P1.2-Pad36)") (class "Default")
      (node (ref "X6") (pin "36") (pinfunction "P1.2_36") (pintype "passive"))
    )
    (net (code "78") (name "unconnected-(X6-P1.4-Pad33)") (class "Default")
      (node (ref "X6") (pin "33") (pinfunction "P1.4_33") (pintype "passive"))
    )
    (net (code "79") (name "unconnected-(X6-P1.6-Pad32)") (class "Default")
      (node (ref "X6") (pin "32") (pinfunction "P1.6_32") (pintype "passive"))
    )
    (net (code "80") (name "unconnected-(X6-P1.7-Pad17)") (class "Default")
      (node (ref "X6") (pin "17") (pinfunction "P1.7_17") (pintype "passive"))
    )
    (net (code "81") (name "unconnected-(X6-P2.0-Pad29)") (class "Default")
      (node (ref "X6") (pin "29") (pinfunction "P2.0_29") (pintype "passive"))
    )
    (net (code "82") (name "unconnected-(X6-P2.2-Pad30)") (class "Default")
      (node (ref "X6") (pin "30") (pinfunction "P2.2_30") (pintype "passive"))
    )
  )
)
